# Nexie_rev_2.net
KiCad netlist of a schematic drawn in Altium Designer
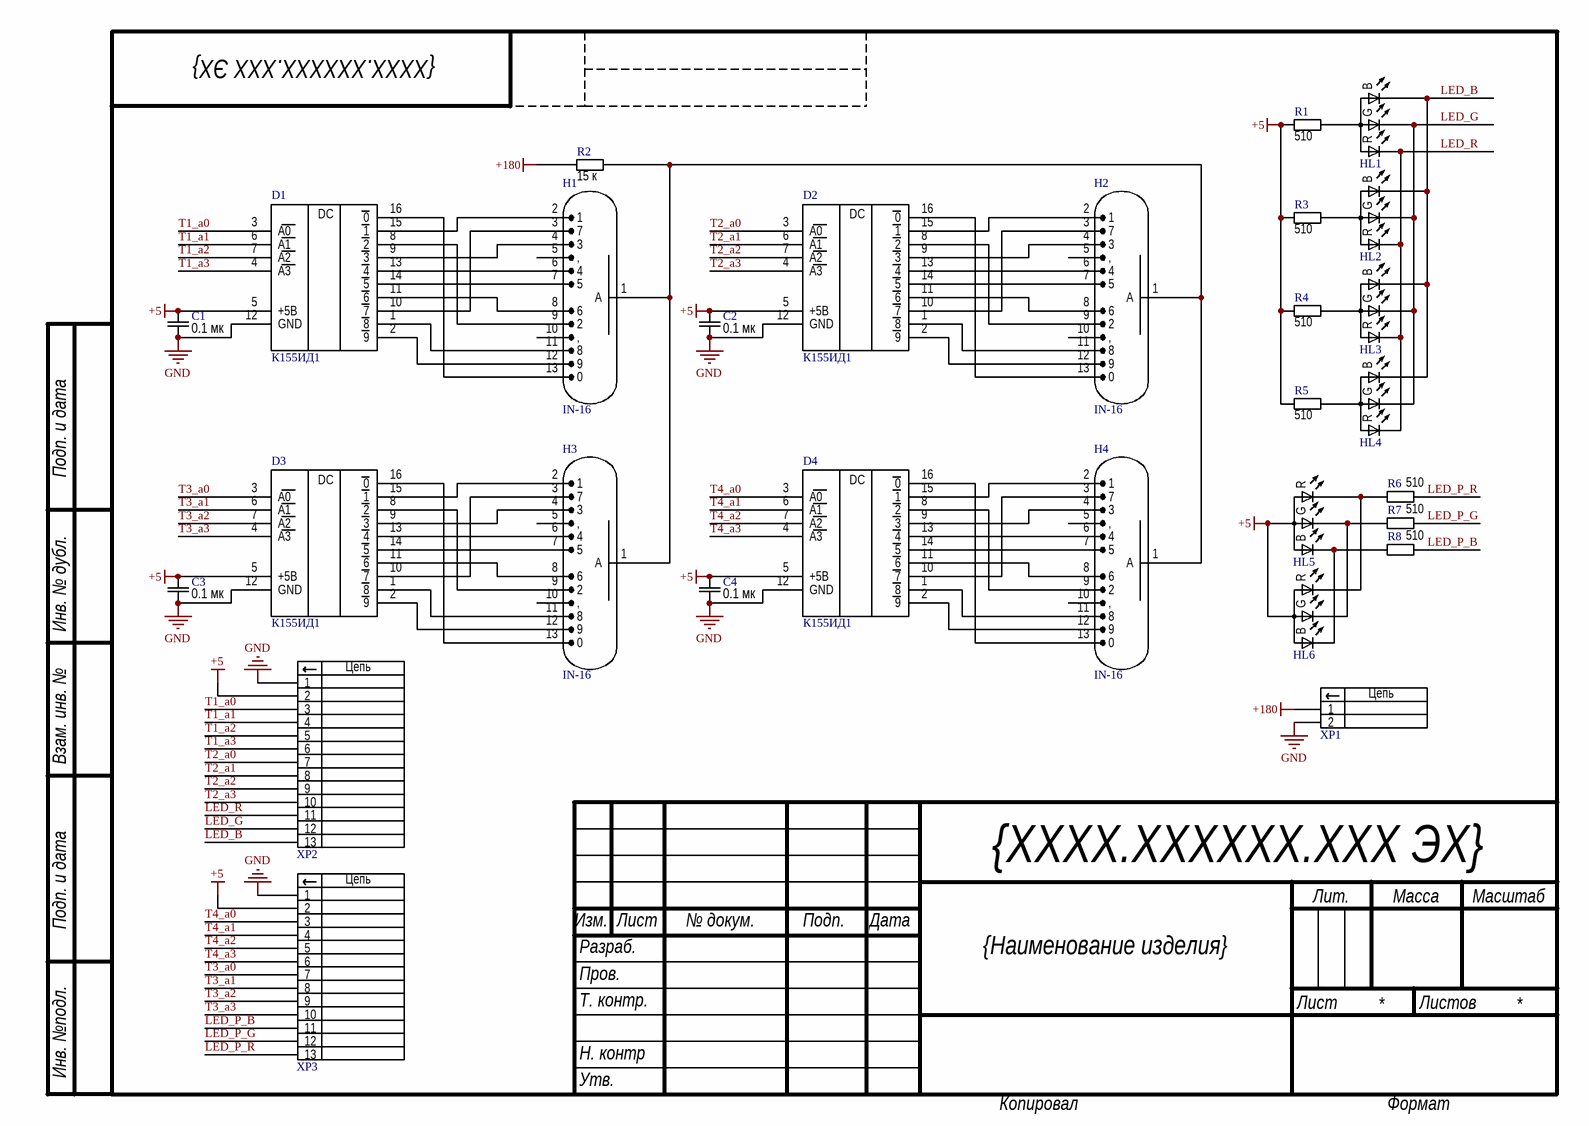
[diagram p0: Nexie rev.2.SchDoc]

(export (version "E")
  (design (tool "Eeschema 10.0.6"))
  (components
    (comp (ref "C1")
      (value "0.1 мк")
      (footprint "SMD_0603")
      (description "Capacitors")
      (fields (field (name "CREATOR") "PavelR"))
      (libsource (lib "Capacitors") (part "Capacitors"))
    )
    (comp (ref "C2")
      (value "0.1 мк")
      (footprint "SMD_0603")
      (description "Capacitors")
      (fields (field (name "CREATOR") "PavelR"))
      (libsource (lib "Capacitors") (part "Capacitors"))
    )
    (comp (ref "C3")
      (value "0.1 мк")
      (footprint "SMD_0603")
      (description "Capacitors")
      (fields (field (name "CREATOR") "PavelR"))
      (libsource (lib "Capacitors") (part "Capacitors"))
    )
    (comp (ref "C4")
      (value "0.1 мк")
      (footprint "SMD_0603")
      (description "Capacitors")
      (fields (field (name "CREATOR") "PavelR"))
      (libsource (lib "Capacitors") (part "Capacitors"))
    )
    (comp (ref "D1") (value "К155ИД1") (footprint "К155ИД1") (libsource (lib "K155") (part "К155ИД1")))
    (comp (ref "D2") (value "К155ИД1") (footprint "К155ИД1") (libsource (lib "K155") (part "К155ИД1")))
    (comp (ref "D3") (value "К155ИД1") (footprint "К155ИД1") (libsource (lib "K155") (part "К155ИД1")))
    (comp (ref "D4") (value "К155ИД1") (footprint "К155ИД1") (libsource (lib "K155") (part "К155ИД1")))
    (comp (ref "H1")
      (value "IN-16")
      (footprint "IN_16_tube")
      (fields (field (name "MANUFACTURER") "СССР"))
      (libsource (lib "TubeIndication") (part "IN-16"))
    )
    (comp (ref "H2")
      (value "IN-16")
      (footprint "IN_16_tube")
      (fields (field (name "MANUFACTURER") "СССР"))
      (libsource (lib "TubeIndication") (part "IN-16"))
    )
    (comp (ref "H3")
      (value "IN-16")
      (footprint "IN_16_tube")
      (fields (field (name "MANUFACTURER") "СССР"))
      (libsource (lib "TubeIndication") (part "IN-16"))
    )
    (comp (ref "H4")
      (value "IN-16")
      (footprint "IN_16_tube")
      (fields (field (name "MANUFACTURER") "СССР"))
      (libsource (lib "TubeIndication") (part "IN-16"))
    )
    (comp (ref "HL1")
      (value "TO-3228BC-MRPBFGF")
      (footprint "TO-3228BC-MRPBFGF")
      (fields
        (field (name "MANUFACTURER") "Taiwan Oasis Technology Co., Ltd")
        (field (name "CREATOR") "FedorenkoS")
      )
      (libsource (lib "LEDs") (part "TO-3228BC-MRPBFGF"))
    )
    (comp (ref "HL2")
      (value "TO-3228BC-MRPBFGF")
      (footprint "TO-3228BC-MRPBFGF")
      (fields
        (field (name "MANUFACTURER") "Taiwan Oasis Technology Co., Ltd")
        (field (name "CREATOR") "FedorenkoS")
      )
      (libsource (lib "LEDs") (part "TO-3228BC-MRPBFGF"))
    )
    (comp (ref "HL3")
      (value "TO-3228BC-MRPBFGF")
      (footprint "TO-3228BC-MRPBFGF")
      (fields
        (field (name "MANUFACTURER") "Taiwan Oasis Technology Co., Ltd")
        (field (name "CREATOR") "FedorenkoS")
      )
      (libsource (lib "LEDs") (part "TO-3228BC-MRPBFGF"))
    )
    (comp (ref "HL4")
      (value "TO-3228BC-MRPBFGF")
      (footprint "TO-3228BC-MRPBFGF")
      (fields
        (field (name "MANUFACTURER") "Taiwan Oasis Technology Co., Ltd")
        (field (name "CREATOR") "FedorenkoS")
      )
      (libsource (lib "LEDs") (part "TO-3228BC-MRPBFGF"))
    )
    (comp (ref "HL5")
      (value "BL-L515RGBC")
      (footprint "BL-L515RGBC")
      (fields (field (name "MANUFACTURER") "Betlux") (field (name "CREATOR") "FedorenkoS"))
      (libsource (lib "LEDs") (part "BL-L515RGBC"))
    )
    (comp (ref "HL6")
      (value "BL-L515RGBC")
      (footprint "BL-L515RGBC")
      (fields (field (name "MANUFACTURER") "Betlux") (field (name "CREATOR") "FedorenkoS"))
      (libsource (lib "LEDs") (part "BL-L515RGBC"))
    )
    (comp (ref "R1")
      (value "510")
      (footprint "SMD_0402")
      (fields (field (name "Comment") "Resistor") (field (name "CREATOR") "PavelR"))
      (libsource (lib "Resistors") (part "Resistor"))
    )
    (comp (ref "R2")
      (value "15 к")
      (footprint "SMD_2512")
      (fields (field (name "Comment") "Resistor") (field (name "CREATOR") "PavelR"))
      (libsource (lib "Resistors") (part "Resistor"))
    )
    (comp (ref "R3")
      (value "510")
      (footprint "SMD_0402")
      (fields (field (name "Comment") "Resistor") (field (name "CREATOR") "PavelR"))
      (libsource (lib "Resistors") (part "Resistor"))
    )
    (comp (ref "R4")
      (value "510")
      (footprint "SMD_0402")
      (fields (field (name "Comment") "Resistor") (field (name "CREATOR") "PavelR"))
      (libsource (lib "Resistors") (part "Resistor"))
    )
    (comp (ref "R5")
      (value "510")
      (footprint "SMD_0402")
      (fields (field (name "Comment") "Resistor") (field (name "CREATOR") "PavelR"))
      (libsource (lib "Resistors") (part "Resistor"))
    )
    (comp (ref "R6")
      (value "510")
      (footprint "SMD_0402")
      (fields (field (name "Comment") "Resistor") (field (name "CREATOR") "PavelR"))
      (libsource (lib "Resistors") (part "Resistor"))
    )
    (comp (ref "R7")
      (value "510")
      (footprint "SMD_0402")
      (fields (field (name "Comment") "Resistor") (field (name "CREATOR") "PavelR"))
      (libsource (lib "Resistors") (part "Resistor"))
    )
    (comp (ref "R8")
      (value "510")
      (footprint "SMD_0402")
      (fields (field (name "Comment") "Resistor") (field (name "CREATOR") "PavelR"))
      (libsource (lib "Resistors") (part "Resistor"))
    )
    (comp (ref "XP1")
      (value "DS1021-1*2SF11")
      (footprint "DS1021-1*2")
      (fields (field (name "РАЗРАБОТЧИК БИБЛИОТЕКИ") "Федоренко С.С."))
      (libsource (lib "Connectors") (part "DS1021-1*2SF11"))
    )
    (comp (ref "XP2")
      (value "DS1021-1*13SF11")
      (footprint "DS1021-1*13")
      (description "PLS")
      (fields (field (name "РАЗРАБОТЧИК БИБЛИОТЕКИ") "Федоренко С.С."))
      (libsource (lib "Connectors") (part "DS1021-1*13SF11"))
    )
    (comp (ref "XP3")
      (value "DS1021-1*13SF11")
      (footprint "DS1021-1*13")
      (description "PLS")
      (fields (field (name "РАЗРАБОТЧИК БИБЛИОТЕКИ") "Федоренко С.С."))
      (libsource (lib "Connectors") (part "DS1021-1*13SF11"))
    )
  )
  (nets
    (net (code "1") (name "+5") (class "Default")
      (node (ref "C1") (pin "2") (pinfunction "2_2") (pintype "passive"))
      (node (ref "C2") (pin "2") (pinfunction "2_2") (pintype "passive"))
      (node (ref "C3") (pin "2") (pinfunction "2_2") (pintype "passive"))
      (node (ref "C4") (pin "2") (pinfunction "2_2") (pintype "passive"))
      (node (ref "D1") (pin "5") (pinfunction "+5В_5") (pintype "passive"))
      (node (ref "D2") (pin "5") (pinfunction "+5В_5") (pintype "passive"))
      (node (ref "D3") (pin "5") (pinfunction "+5В_5") (pintype "passive"))
      (node (ref "D4") (pin "5") (pinfunction "+5В_5") (pintype "passive"))
      (node (ref "HL5") (pin "3") (pinfunction "A_3") (pintype "passive"))
      (node (ref "HL6") (pin "3") (pinfunction "A_3") (pintype "passive"))
      (node (ref "R1") (pin "1") (pinfunction "1_1") (pintype "passive"))
      (node (ref "R3") (pin "1") (pinfunction "1_1") (pintype "passive"))
      (node (ref "R4") (pin "1") (pinfunction "1_1") (pintype "passive"))
      (node (ref "R5") (pin "1") (pinfunction "1_1") (pintype "passive"))
      (node (ref "XP2") (pin "2") (pinfunction "2_2") (pintype "passive"))
      (node (ref "XP3") (pin "2") (pinfunction "2_2") (pintype "passive"))
    )
    (net (code "2") (name "+180") (class "Default")
      (node (ref "R2") (pin "1") (pinfunction "1_1") (pintype "passive"))
      (node (ref "XP1") (pin "1") (pinfunction "1_1") (pintype "passive"))
    )
    (net (code "3") (name "/LED_B") (class "Default")
      (node (ref "HL1") (pin "3") (pinfunction "R_3") (pintype "passive"))
      (node (ref "HL2") (pin "3") (pinfunction "R_3") (pintype "passive"))
      (node (ref "HL3") (pin "3") (pinfunction "R_3") (pintype "passive"))
      (node (ref "HL4") (pin "3") (pinfunction "R_3") (pintype "passive"))
      (node (ref "XP2") (pin "13") (pinfunction "13_13") (pintype "passive"))
    )
    (net (code "4") (name "/LED_G") (class "Default")
      (node (ref "HL1") (pin "2") (pinfunction "G_2") (pintype "passive"))
      (node (ref "HL2") (pin "2") (pinfunction "G_2") (pintype "passive"))
      (node (ref "HL3") (pin "2") (pinfunction "G_2") (pintype "passive"))
      (node (ref "HL4") (pin "2") (pinfunction "G_2") (pintype "passive"))
      (node (ref "XP2") (pin "12") (pinfunction "12_12") (pintype "passive"))
    )
    (net (code "5") (name "/LED_P_B") (class "Default")
      (node (ref "R8") (pin "2") (pinfunction "2_2") (pintype "passive"))
      (node (ref "XP3") (pin "11") (pinfunction "11_11") (pintype "passive"))
    )
    (net (code "6") (name "/LED_P_G") (class "Default")
      (node (ref "R7") (pin "2") (pinfunction "2_2") (pintype "passive"))
      (node (ref "XP3") (pin "12") (pinfunction "12_12") (pintype "passive"))
    )
    (net (code "7") (name "/LED_P_R") (class "Default")
      (node (ref "R6") (pin "2") (pinfunction "2_2") (pintype "passive"))
      (node (ref "XP3") (pin "13") (pinfunction "13_13") (pintype "passive"))
    )
    (net (code "8") (name "/LED_R") (class "Default")
      (node (ref "HL1") (pin "1") (pinfunction "R_1") (pintype "passive"))
      (node (ref "HL2") (pin "1") (pinfunction "R_1") (pintype "passive"))
      (node (ref "HL3") (pin "1") (pinfunction "R_1") (pintype "passive"))
      (node (ref "HL4") (pin "1") (pinfunction "R_1") (pintype "passive"))
      (node (ref "XP2") (pin "11") (pinfunction "11_11") (pintype "passive"))
    )
    (net (code "9") (name "/T1_a0") (class "Default")
      (node (ref "D1") (pin "3") (pinfunction "А0_3") (pintype "passive"))
      (node (ref "XP2") (pin "3") (pinfunction "3_3") (pintype "passive"))
    )
    (net (code "10") (name "/T1_a1") (class "Default")
      (node (ref "D1") (pin "6") (pinfunction "А1_6") (pintype "passive"))
      (node (ref "XP2") (pin "4") (pinfunction "4_4") (pintype "passive"))
    )
    (net (code "11") (name "/T1_a2") (class "Default")
      (node (ref "D1") (pin "7") (pinfunction "А2_7") (pintype "passive"))
      (node (ref "XP2") (pin "5") (pinfunction "5_5") (pintype "passive"))
    )
    (net (code "12") (name "/T1_a3") (class "Default")
      (node (ref "D1") (pin "4") (pinfunction "А3_4") (pintype "passive"))
      (node (ref "XP2") (pin "6") (pinfunction "6_6") (pintype "passive"))
    )
    (net (code "13") (name "/T2_a0") (class "Default")
      (node (ref "D2") (pin "3") (pinfunction "А0_3") (pintype "passive"))
      (node (ref "XP2") (pin "7") (pinfunction "7_7") (pintype "passive"))
    )
    (net (code "14") (name "/T2_a1") (class "Default")
      (node (ref "D2") (pin "6") (pinfunction "А1_6") (pintype "passive"))
      (node (ref "XP2") (pin "8") (pinfunction "8_8") (pintype "passive"))
    )
    (net (code "15") (name "/T2_a2") (class "Default")
      (node (ref "D2") (pin "7") (pinfunction "А2_7") (pintype "passive"))
      (node (ref "XP2") (pin "9") (pinfunction "9_9") (pintype "passive"))
    )
    (net (code "16") (name "/T2_a3") (class "Default")
      (node (ref "D2") (pin "4") (pinfunction "А3_4") (pintype "passive"))
      (node (ref "XP2") (pin "10") (pinfunction "10_10") (pintype "passive"))
    )
    (net (code "17") (name "/T3_a0") (class "Default")
      (node (ref "D3") (pin "3") (pinfunction "А0_3") (pintype "passive"))
      (node (ref "XP3") (pin "7") (pinfunction "7_7") (pintype "passive"))
    )
    (net (code "18") (name "/T3_a1") (class "Default")
      (node (ref "D3") (pin "6") (pinfunction "А1_6") (pintype "passive"))
      (node (ref "XP3") (pin "8") (pinfunction "8_8") (pintype "passive"))
    )
    (net (code "19") (name "/T3_a2") (class "Default")
      (node (ref "D3") (pin "7") (pinfunction "А2_7") (pintype "passive"))
      (node (ref "XP3") (pin "9") (pinfunction "9_9") (pintype "passive"))
    )
    (net (code "20") (name "/T3_a3") (class "Default")
      (node (ref "D3") (pin "4") (pinfunction "А3_4") (pintype "passive"))
      (node (ref "XP3") (pin "10") (pinfunction "10_10") (pintype "passive"))
    )
    (net (code "21") (name "/T4_a0") (class "Default")
      (node (ref "D4") (pin "3") (pinfunction "А0_3") (pintype "passive"))
      (node (ref "XP3") (pin "3") (pinfunction "3_3") (pintype "passive"))
    )
    (net (code "22") (name "/T4_a1") (class "Default")
      (node (ref "D4") (pin "6") (pinfunction "А1_6") (pintype "passive"))
      (node (ref "XP3") (pin "4") (pinfunction "4_4") (pintype "passive"))
    )
    (net (code "23") (name "/T4_a2") (class "Default")
      (node (ref "D4") (pin "7") (pinfunction "А2_7") (pintype "passive"))
      (node (ref "XP3") (pin "5") (pinfunction "5_5") (pintype "passive"))
    )
    (net (code "24") (name "/T4_a3") (class "Default")
      (node (ref "D4") (pin "4") (pinfunction "А3_4") (pintype "passive"))
      (node (ref "XP3") (pin "6") (pinfunction "6_6") (pintype "passive"))
    )
    (net (code "25") (name "GND") (class "Default")
      (node (ref "C1") (pin "1") (pinfunction "1_1") (pintype "passive"))
      (node (ref "C2") (pin "1") (pinfunction "1_1") (pintype "passive"))
      (node (ref "C3") (pin "1") (pinfunction "1_1") (pintype "passive"))
      (node (ref "C4") (pin "1") (pinfunction "1_1") (pintype "passive"))
      (node (ref "D1") (pin "12") (pinfunction "GND_12") (pintype "passive"))
      (node (ref "D2") (pin "12") (pinfunction "GND_12") (pintype "passive"))
      (node (ref "D3") (pin "12") (pinfunction "GND_12") (pintype "passive"))
      (node (ref "D4") (pin "12") (pinfunction "GND_12") (pintype "passive"))
      (node (ref "XP1") (pin "2") (pinfunction "2_2") (pintype "passive"))
      (node (ref "XP2") (pin "1") (pinfunction "1_1") (pintype "passive"))
      (node (ref "XP3") (pin "1") (pinfunction "1_1") (pintype "passive"))
    )
    (net (code "26") (name "Net-(D1-0)") (class "Default")
      (node (ref "D1") (pin "16") (pinfunction "0_16") (pintype "passive"))
      (node (ref "H1") (pin "13") (pinfunction "0_13") (pintype "passive"))
    )
    (net (code "27") (name "Net-(D1-1)") (class "Default")
      (node (ref "D1") (pin "15") (pinfunction "1_15") (pintype "passive"))
      (node (ref "H1") (pin "2") (pinfunction "1_2") (pintype "passive"))
    )
    (net (code "28") (name "Net-(D1-2)") (class "Default")
      (node (ref "D1") (pin "8") (pinfunction "2_8") (pintype "passive"))
      (node (ref "H1") (pin "9") (pinfunction "2_9") (pintype "passive"))
    )
    (net (code "29") (name "Net-(D1-3)") (class "Default")
      (node (ref "D1") (pin "9") (pinfunction "3_9") (pintype "passive"))
      (node (ref "H1") (pin "4") (pinfunction "3_4") (pintype "passive"))
    )
    (net (code "30") (name "Net-(D1-4)") (class "Default")
      (node (ref "D1") (pin "13") (pinfunction "4_13") (pintype "passive"))
      (node (ref "H1") (pin "6") (pinfunction "4_6") (pintype "passive"))
    )
    (net (code "31") (name "Net-(D1-5)") (class "Default")
      (node (ref "D1") (pin "14") (pinfunction "5_14") (pintype "passive"))
      (node (ref "H1") (pin "7") (pinfunction "5_7") (pintype "passive"))
    )
    (net (code "32") (name "Net-(D1-6)") (class "Default")
      (node (ref "D1") (pin "11") (pinfunction "6_11") (pintype "passive"))
      (node (ref "H1") (pin "8") (pinfunction "6_8") (pintype "passive"))
    )
    (net (code "33") (name "Net-(D1-7)") (class "Default")
      (node (ref "D1") (pin "10") (pinfunction "7_10") (pintype "passive"))
      (node (ref "H1") (pin "3") (pinfunction "7_3") (pintype "passive"))
    )
    (net (code "34") (name "Net-(D1-8)") (class "Default")
      (node (ref "D1") (pin "1") (pinfunction "8_1") (pintype "passive"))
      (node (ref "H1") (pin "11") (pinfunction "8_11") (pintype "passive"))
    )
    (net (code "35") (name "Net-(D1-9)") (class "Default")
      (node (ref "D1") (pin "2") (pinfunction "9_2") (pintype "passive"))
      (node (ref "H1") (pin "12") (pinfunction "9_12") (pintype "passive"))
    )
    (net (code "36") (name "Net-(D2-0)") (class "Default")
      (node (ref "D2") (pin "16") (pinfunction "0_16") (pintype "passive"))
      (node (ref "H2") (pin "13") (pinfunction "0_13") (pintype "passive"))
    )
    (net (code "37") (name "Net-(D2-1)") (class "Default")
      (node (ref "D2") (pin "15") (pinfunction "1_15") (pintype "passive"))
      (node (ref "H2") (pin "2") (pinfunction "1_2") (pintype "passive"))
    )
    (net (code "38") (name "Net-(D2-2)") (class "Default")
      (node (ref "D2") (pin "8") (pinfunction "2_8") (pintype "passive"))
      (node (ref "H2") (pin "9") (pinfunction "2_9") (pintype "passive"))
    )
    (net (code "39") (name "Net-(D2-3)") (class "Default")
      (node (ref "D2") (pin "9") (pinfunction "3_9") (pintype "passive"))
      (node (ref "H2") (pin "4") (pinfunction "3_4") (pintype "passive"))
    )
    (net (code "40") (name "Net-(D2-4)") (class "Default")
      (node (ref "D2") (pin "13") (pinfunction "4_13") (pintype "passive"))
      (node (ref "H2") (pin "6") (pinfunction "4_6") (pintype "passive"))
    )
    (net (code "41") (name "Net-(D2-5)") (class "Default")
      (node (ref "D2") (pin "14") (pinfunction "5_14") (pintype "passive"))
      (node (ref "H2") (pin "7") (pinfunction "5_7") (pintype "passive"))
    )
    (net (code "42") (name "Net-(D2-6)") (class "Default")
      (node (ref "D2") (pin "11") (pinfunction "6_11") (pintype "passive"))
      (node (ref "H2") (pin "8") (pinfunction "6_8") (pintype "passive"))
    )
    (net (code "43") (name "Net-(D2-7)") (class "Default")
      (node (ref "D2") (pin "10") (pinfunction "7_10") (pintype "passive"))
      (node (ref "H2") (pin "3") (pinfunction "7_3") (pintype "passive"))
    )
    (net (code "44") (name "Net-(D2-8)") (class "Default")
      (node (ref "D2") (pin "1") (pinfunction "8_1") (pintype "passive"))
      (node (ref "H2") (pin "11") (pinfunction "8_11") (pintype "passive"))
    )
    (net (code "45") (name "Net-(D2-9)") (class "Default")
      (node (ref "D2") (pin "2") (pinfunction "9_2") (pintype "passive"))
      (node (ref "H2") (pin "12") (pinfunction "9_12") (pintype "passive"))
    )
    (net (code "46") (name "Net-(D3-0)") (class "Default")
      (node (ref "D3") (pin "16") (pinfunction "0_16") (pintype "passive"))
      (node (ref "H3") (pin "13") (pinfunction "0_13") (pintype "passive"))
    )
    (net (code "47") (name "Net-(D3-1)") (class "Default")
      (node (ref "D3") (pin "15") (pinfunction "1_15") (pintype "passive"))
      (node (ref "H3") (pin "2") (pinfunction "1_2") (pintype "passive"))
    )
    (net (code "48") (name "Net-(D3-2)") (class "Default")
      (node (ref "D3") (pin "8") (pinfunction "2_8") (pintype "passive"))
      (node (ref "H3") (pin "9") (pinfunction "2_9") (pintype "passive"))
    )
    (net (code "49") (name "Net-(D3-3)") (class "Default")
      (node (ref "D3") (pin "9") (pinfunction "3_9") (pintype "passive"))
      (node (ref "H3") (pin "4") (pinfunction "3_4") (pintype "passive"))
    )
    (net (code "50") (name "Net-(D3-4)") (class "Default")
      (node (ref "D3") (pin "13") (pinfunction "4_13") (pintype "passive"))
      (node (ref "H3") (pin "6") (pinfunction "4_6") (pintype "passive"))
    )
    (net (code "51") (name "Net-(D3-5)") (class "Default")
      (node (ref "D3") (pin "14") (pinfunction "5_14") (pintype "passive"))
      (node (ref "H3") (pin "7") (pinfunction "5_7") (pintype "passive"))
    )
    (net (code "52") (name "Net-(D3-6)") (class "Default")
      (node (ref "D3") (pin "11") (pinfunction "6_11") (pintype "passive"))
      (node (ref "H3") (pin "8") (pinfunction "6_8") (pintype "passive"))
    )
    (net (code "53") (name "Net-(D3-7)") (class "Default")
      (node (ref "D3") (pin "10") (pinfunction "7_10") (pintype "passive"))
      (node (ref "H3") (pin "3") (pinfunction "7_3") (pintype "passive"))
    )
    (net (code "54") (name "Net-(D3-8)") (class "Default")
      (node (ref "D3") (pin "1") (pinfunction "8_1") (pintype "passive"))
      (node (ref "H3") (pin "11") (pinfunction "8_11") (pintype "passive"))
    )
    (net (code "55") (name "Net-(D3-9)") (class "Default")
      (node (ref "D3") (pin "2") (pinfunction "9_2") (pintype "passive"))
      (node (ref "H3") (pin "12") (pinfunction "9_12") (pintype "passive"))
    )
    (net (code "56") (name "Net-(D4-0)") (class "Default")
      (node (ref "D4") (pin "16") (pinfunction "0_16") (pintype "passive"))
      (node (ref "H4") (pin "13") (pinfunction "0_13") (pintype "passive"))
    )
    (net (code "57") (name "Net-(D4-1)") (class "Default")
      (node (ref "D4") (pin "15") (pinfunction "1_15") (pintype "passive"))
      (node (ref "H4") (pin "2") (pinfunction "1_2") (pintype "passive"))
    )
    (net (code "58") (name "Net-(D4-2)") (class "Default")
      (node (ref "D4") (pin "8") (pinfunction "2_8") (pintype "passive"))
      (node (ref "H4") (pin "9") (pinfunction "2_9") (pintype "passive"))
    )
    (net (code "59") (name "Net-(D4-3)") (class "Default")
      (node (ref "D4") (pin "9") (pinfunction "3_9") (pintype "passive"))
      (node (ref "H4") (pin "4") (pinfunction "3_4") (pintype "passive"))
    )
    (net (code "60") (name "Net-(D4-4)") (class "Default")
      (node (ref "D4") (pin "13") (pinfunction "4_13") (pintype "passive"))
      (node (ref "H4") (pin "6") (pinfunction "4_6") (pintype "passive"))
    )
    (net (code "61") (name "Net-(D4-5)") (class "Default")
      (node (ref "D4") (pin "14") (pinfunction "5_14") (pintype "passive"))
      (node (ref "H4") (pin "7") (pinfunction "5_7") (pintype "passive"))
    )
    (net (code "62") (name "Net-(D4-6)") (class "Default")
      (node (ref "D4") (pin "11") (pinfunction "6_11") (pintype "passive"))
      (node (ref "H4") (pin "8") (pinfunction "6_8") (pintype "passive"))
    )
    (net (code "63") (name "Net-(D4-7)") (class "Default")
      (node (ref "D4") (pin "10") (pinfunction "7_10") (pintype "passive"))
      (node (ref "H4") (pin "3") (pinfunction "7_3") (pintype "passive"))
    )
    (net (code "64") (name "Net-(D4-8)") (class "Default")
      (node (ref "D4") (pin "1") (pinfunction "8_1") (pintype "passive"))
      (node (ref "H4") (pin "11") (pinfunction "8_11") (pintype "passive"))
    )
    (net (code "65") (name "Net-(D4-9)") (class "Default")
      (node (ref "D4") (pin "2") (pinfunction "9_2") (pintype "passive"))
      (node (ref "H4") (pin "12") (pinfunction "9_12") (pintype "passive"))
    )
    (net (code "66") (name "Net-(H1-A)") (class "Default")
      (node (ref "H1") (pin "1") (pinfunction "A_1") (pintype "passive"))
      (node (ref "H2") (pin "1") (pinfunction "A_1") (pintype "passive"))
      (node (ref "H3") (pin "1") (pinfunction "A_1") (pintype "passive"))
      (node (ref "H4") (pin "1") (pinfunction "A_1") (pintype "passive"))
      (node (ref "R2") (pin "2") (pinfunction "2_2") (pintype "passive"))
    )
    (net (code "67") (name "Net-(HL1-A)") (class "Default")
      (node (ref "HL1") (pin "4") (pinfunction "A_4") (pintype "passive"))
      (node (ref "R1") (pin "2") (pinfunction "2_2") (pintype "passive"))
    )
    (net (code "68") (name "Net-(HL2-A)") (class "Default")
      (node (ref "HL2") (pin "4") (pinfunction "A_4") (pintype "passive"))
      (node (ref "R3") (pin "2") (pinfunction "2_2") (pintype "passive"))
    )
    (net (code "69") (name "Net-(HL3-A)") (class "Default")
      (node (ref "HL3") (pin "4") (pinfunction "A_4") (pintype "passive"))
      (node (ref "R4") (pin "2") (pinfunction "2_2") (pintype "passive"))
    )
    (net (code "70") (name "Net-(HL4-A)") (class "Default")
      (node (ref "HL4") (pin "4") (pinfunction "A_4") (pintype "passive"))
      (node (ref "R5") (pin "2") (pinfunction "2_2") (pintype "passive"))
    )
    (net (code "71") (name "Net-(HL5-B)") (class "Default")
      (node (ref "HL5") (pin "1") (pinfunction "B_1") (pintype "passive"))
      (node (ref "HL6") (pin "1") (pinfunction "B_1") (pintype "passive"))
      (node (ref "R8") (pin "1") (pinfunction "1_1") (pintype "passive"))
    )
    (net (code "72") (name "Net-(HL5-G)") (class "Default")
      (node (ref "HL5") (pin "2") (pinfunction "G_2") (pintype "passive"))
      (node (ref "HL6") (pin "2") (pinfunction "G_2") (pintype "passive"))
      (node (ref "R7") (pin "1") (pinfunction "1_1") (pintype "passive"))
    )
    (net (code "73") (name "Net-(HL5-R)") (class "Default")
      (node (ref "HL5") (pin "4") (pinfunction "R_4") (pintype "passive"))
      (node (ref "HL6") (pin "4") (pinfunction "R_4") (pintype "passive"))
      (node (ref "R6") (pin "1") (pinfunction "1_1") (pintype "passive"))
    )
    (net (code "74") (name "unconnected-(H1-,-Pad5)") (class "Default")
      (node (ref "H1") (pin "5") (pinfunction ",_5") (pintype "passive"))
    )
    (net (code "75") (name "unconnected-(H1-,-Pad10)") (class "Default")
      (node (ref "H1") (pin "10") (pinfunction ",_10") (pintype "passive"))
    )
    (net (code "76") (name "unconnected-(H2-,-Pad5)") (class "Default")
      (node (ref "H2") (pin "5") (pinfunction ",_5") (pintype "passive"))
    )
    (net (code "77") (name "unconnected-(H2-,-Pad10)") (class "Default")
      (node (ref "H2") (pin "10") (pinfunction ",_10") (pintype "passive"))
    )
    (net (code "78") (name "unconnected-(H3-,-Pad5)") (class "Default")
      (node (ref "H3") (pin "5") (pinfunction ",_5") (pintype "passive"))
    )
    (net (code "79") (name "unconnected-(H3-,-Pad10)") (class "Default")
      (node (ref "H3") (pin "10") (pinfunction ",_10") (pintype "passive"))
    )
    (net (code "80") (name "unconnected-(H4-,-Pad5)") (class "Default")
      (node (ref "H4") (pin "5") (pinfunction ",_5") (pintype "passive"))
    )
    (net (code "81") (name "unconnected-(H4-,-Pad10)") (class "Default")
      (node (ref "H4") (pin "10") (pinfunction ",_10") (pintype "passive"))
    )
  )
)
